# Buck_Sense.net
KiCad netlist of a schematic drawn in Altium Designer
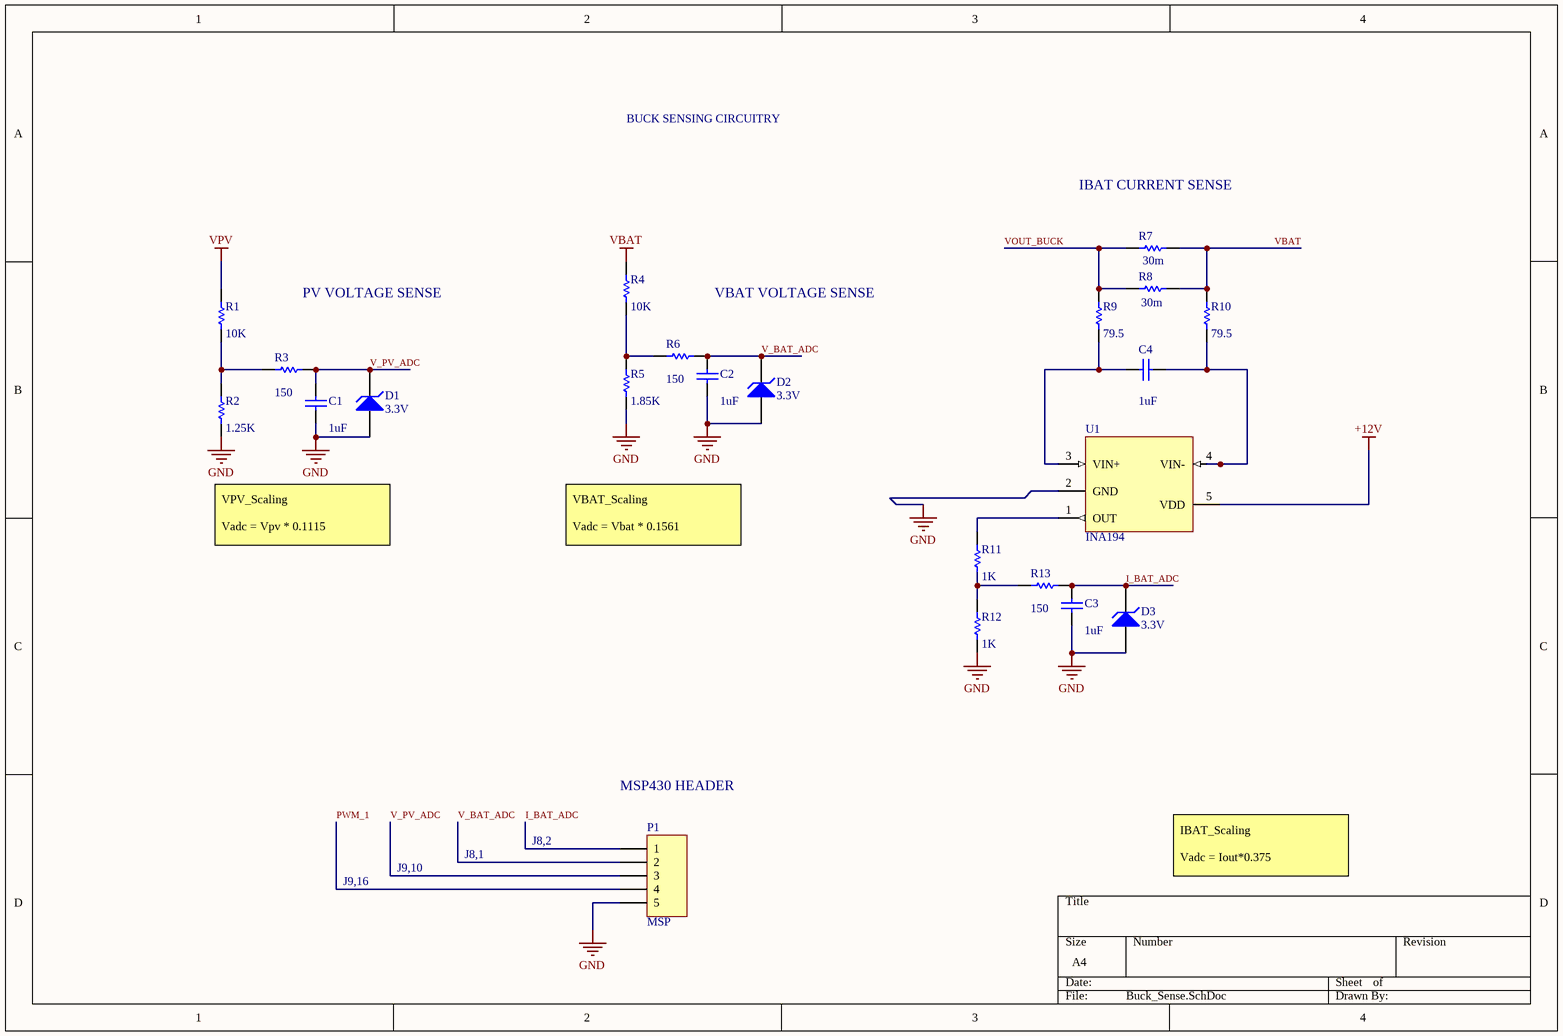
[diagram p0: Buck_Sense.SchDoc]

(export (version "E")
  (design (tool "Eeschema 10.0.6"))
  (components
    (comp (ref "C1")
      (value "1uF")
      (footprint "RAD-0.3")
      (description "Capacitor")
      (fields (field (name "PUBLISHER") "Altium Limited"))
      (libsource (lib "Miscellaneous Devices") (part "Cap"))
    )
    (comp (ref "C2")
      (value "1uF")
      (footprint "RAD-0.3")
      (description "Capacitor")
      (fields (field (name "PUBLISHER") "Altium Limited"))
      (libsource (lib "Miscellaneous Devices") (part "Cap"))
    )
    (comp (ref "C3")
      (value "1uF")
      (footprint "RAD-0.3")
      (description "Capacitor")
      (fields (field (name "PUBLISHER") "Altium Limited"))
      (libsource (lib "Miscellaneous Devices") (part "Cap"))
    )
    (comp (ref "C4")
      (value "1uF")
      (footprint "RAD-0.3")
      (description "Capacitor")
      (fields (field (name "PUBLISHER") "Altium Limited"))
      (libsource (lib "Miscellaneous Devices") (part "Cap"))
    )
    (comp (ref "D1")
      (value "3.3V")
      (footprint "DIODE-0.7")
      (description "Zener Diode")
      (fields (field (name "PUBLISHER") "Altium Limited"))
      (libsource (lib "Miscellaneous Devices") (part "D Zener"))
    )
    (comp (ref "D2")
      (value "3.3V")
      (footprint "DIODE-0.7")
      (description "Zener Diode")
      (fields (field (name "PUBLISHER") "Altium Limited"))
      (libsource (lib "Miscellaneous Devices") (part "D Zener"))
    )
    (comp (ref "D3")
      (value "3.3V")
      (footprint "DIODE-0.7")
      (description "Zener Diode")
      (fields (field (name "PUBLISHER") "Altium Limited"))
      (libsource (lib "Miscellaneous Devices") (part "D Zener"))
    )
    (comp (ref "P1")
      (value "MSP")
      (footprint "HDR1X5")
      (description "Header, 5-Pin")
      (fields (field (name "PUBLISHER") "Altium Limited"))
      (libsource (lib "Miscellaneous Connectors") (part "Header 5"))
    )
    (comp (ref "R1")
      (value "10K")
      (footprint "AXIAL-0.3")
      (description "Resistor")
      (fields (field (name "PUBLISHER") "Altium Limited"))
      (libsource (lib "Miscellaneous Devices") (part "Res1"))
    )
    (comp (ref "R2")
      (value "1.25K")
      (footprint "AXIAL-0.3")
      (description "Resistor")
      (fields (field (name "PUBLISHER") "Altium Limited"))
      (libsource (lib "Miscellaneous Devices") (part "Res1"))
    )
    (comp (ref "R3")
      (value "150")
      (footprint "AXIAL-0.3")
      (description "Resistor")
      (fields (field (name "PUBLISHER") "Altium Limited"))
      (libsource (lib "Miscellaneous Devices") (part "Res1"))
    )
    (comp (ref "R4")
      (value "10K")
      (footprint "AXIAL-0.3")
      (description "Resistor")
      (fields (field (name "PUBLISHER") "Altium Limited"))
      (libsource (lib "Miscellaneous Devices") (part "Res1"))
    )
    (comp (ref "R5")
      (value "1.85K")
      (footprint "AXIAL-0.3")
      (description "Resistor")
      (fields (field (name "PUBLISHER") "Altium Limited"))
      (libsource (lib "Miscellaneous Devices") (part "Res1"))
    )
    (comp (ref "R6")
      (value "150")
      (footprint "AXIAL-0.3")
      (description "Resistor")
      (fields (field (name "PUBLISHER") "Altium Limited"))
      (libsource (lib "Miscellaneous Devices") (part "Res1"))
    )
    (comp (ref "R7")
      (value "30m")
      (footprint "AXIAL-0.3")
      (description "Resistor")
      (fields (field (name "PUBLISHER") "Altium Limited"))
      (libsource (lib "Miscellaneous Devices") (part "Res1"))
    )
    (comp (ref "R8")
      (value "30m")
      (footprint "AXIAL-0.3")
      (description "Resistor")
      (fields (field (name "PUBLISHER") "Altium Limited"))
      (libsource (lib "Miscellaneous Devices") (part "Res1"))
    )
    (comp (ref "R9")
      (value "79.5")
      (footprint "AXIAL-0.3")
      (description "Resistor")
      (fields (field (name "PUBLISHER") "Altium Limited"))
      (libsource (lib "Miscellaneous Devices") (part "Res1"))
    )
    (comp (ref "R10")
      (value "79.5")
      (footprint "AXIAL-0.3")
      (description "Resistor")
      (fields (field (name "PUBLISHER") "Altium Limited"))
      (libsource (lib "Miscellaneous Devices") (part "Res1"))
    )
    (comp (ref "R11")
      (value "1K")
      (footprint "AXIAL-0.3")
      (description "Resistor")
      (fields (field (name "PUBLISHER") "Altium Limited"))
      (libsource (lib "Miscellaneous Devices") (part "Res1"))
    )
    (comp (ref "R12")
      (value "1K")
      (footprint "AXIAL-0.3")
      (description "Resistor")
      (fields (field (name "PUBLISHER") "Altium Limited"))
      (libsource (lib "Miscellaneous Devices") (part "Res1"))
    )
    (comp (ref "R13")
      (value "150")
      (footprint "AXIAL-0.3")
      (description "Resistor")
      (fields (field (name "PUBLISHER") "Altium Limited"))
      (libsource (lib "Miscellaneous Devices") (part "Res1"))
    )
    (comp (ref "U1")
      (value "INA194")
      (description "CURRENT SHUNT MONITOR")
      (libsource (lib "*") (part "INA194"))
    )
  )
  (nets
    (net (code "1") (name "+12V") (class "Default")
      (node (ref "U1") (pin "5") (pinfunction "VDD_5") (pintype "power_in"))
    )
    (net (code "2") (name "/I_BAT_ADC") (class "Default")
      (node (ref "C3") (pin "2") (pinfunction "2_2") (pintype "passive"))
      (node (ref "D3") (pin "2") (pinfunction "K_2") (pintype "passive"))
      (node (ref "P1") (pin "1") (pinfunction "1_1") (pintype "passive"))
      (node (ref "R13") (pin "2") (pinfunction "2_2") (pintype "passive"))
    )
    (net (code "3") (name "/PWM_1") (class "Default")
      (node (ref "P1") (pin "4") (pinfunction "4_4") (pintype "passive"))
    )
    (net (code "4") (name "/VOUT_BUCK") (class "Default")
      (node (ref "R7") (pin "2") (pinfunction "2_2") (pintype "passive"))
      (node (ref "R8") (pin "2") (pinfunction "2_2") (pintype "passive"))
      (node (ref "R9") (pin "1") (pinfunction "1_1") (pintype "passive"))
    )
    (net (code "5") (name "/V_BAT_ADC") (class "Default")
      (node (ref "C2") (pin "2") (pinfunction "2_2") (pintype "passive"))
      (node (ref "D2") (pin "2") (pinfunction "K_2") (pintype "passive"))
      (node (ref "P1") (pin "2") (pinfunction "2_2") (pintype "passive"))
      (node (ref "R6") (pin "1") (pinfunction "1_1") (pintype "passive"))
    )
    (net (code "6") (name "/V_PV_ADC") (class "Default")
      (node (ref "C1") (pin "2") (pinfunction "2_2") (pintype "passive"))
      (node (ref "D1") (pin "2") (pinfunction "K_2") (pintype "passive"))
      (node (ref "P1") (pin "3") (pinfunction "3_3") (pintype "passive"))
      (node (ref "R3") (pin "2") (pinfunction "2_2") (pintype "passive"))
    )
    (net (code "7") (name "GND") (class "Default")
      (node (ref "C1") (pin "1") (pinfunction "1_1") (pintype "passive"))
      (node (ref "C2") (pin "1") (pinfunction "1_1") (pintype "passive"))
      (node (ref "C3") (pin "1") (pinfunction "1_1") (pintype "passive"))
      (node (ref "D1") (pin "1") (pinfunction "A_1") (pintype "passive"))
      (node (ref "D2") (pin "1") (pinfunction "A_1") (pintype "passive"))
      (node (ref "D3") (pin "1") (pinfunction "A_1") (pintype "passive"))
      (node (ref "P1") (pin "5") (pinfunction "5_5") (pintype "passive"))
      (node (ref "R12") (pin "2") (pinfunction "2_2") (pintype "passive"))
      (node (ref "R2") (pin "1") (pinfunction "1_1") (pintype "passive"))
      (node (ref "R5") (pin "1") (pinfunction "1_1") (pintype "passive"))
      (node (ref "U1") (pin "2") (pinfunction "GND_2") (pintype "power_in"))
    )
    (net (code "8") (name "Net-(R1-Pad1)") (class "Default")
      (node (ref "R1") (pin "1") (pinfunction "1_1") (pintype "passive"))
      (node (ref "R2") (pin "2") (pinfunction "2_2") (pintype "passive"))
      (node (ref "R3") (pin "1") (pinfunction "1_1") (pintype "passive"))
    )
    (net (code "9") (name "Net-(R4-Pad1)") (class "Default")
      (node (ref "R4") (pin "1") (pinfunction "1_1") (pintype "passive"))
      (node (ref "R5") (pin "2") (pinfunction "2_2") (pintype "passive"))
      (node (ref "R6") (pin "2") (pinfunction "2_2") (pintype "passive"))
    )
    (net (code "10") (name "Net-(R11-Pad2)") (class "Default")
      (node (ref "R11") (pin "2") (pinfunction "2_2") (pintype "passive"))
      (node (ref "R12") (pin "1") (pinfunction "1_1") (pintype "passive"))
      (node (ref "R13") (pin "1") (pinfunction "1_1") (pintype "passive"))
    )
    (net (code "11") (name "Net-(U1-OUT)") (class "Default")
      (node (ref "R11") (pin "1") (pinfunction "1_1") (pintype "passive"))
      (node (ref "U1") (pin "1") (pinfunction "OUT_1") (pintype "output"))
    )
    (net (code "12") (name "Net-(U1-VIN+)") (class "Default")
      (node (ref "C4") (pin "2") (pinfunction "2_2") (pintype "passive"))
      (node (ref "R9") (pin "2") (pinfunction "2_2") (pintype "passive"))
      (node (ref "U1") (pin "3") (pinfunction "VIN+_3") (pintype "input"))
    )
    (net (code "13") (name "Net-(U1-VIN-)") (class "Default")
      (node (ref "C4") (pin "1") (pinfunction "1_1") (pintype "passive"))
      (node (ref "R10") (pin "2") (pinfunction "2_2") (pintype "passive"))
      (node (ref "U1") (pin "4") (pinfunction "VIN-_4") (pintype "input"))
    )
    (net (code "14") (name "VBAT") (class "Default")
      (node (ref "R10") (pin "1") (pinfunction "1_1") (pintype "passive"))
      (node (ref "R4") (pin "2") (pinfunction "2_2") (pintype "passive"))
      (node (ref "R7") (pin "1") (pinfunction "1_1") (pintype "passive"))
      (node (ref "R8") (pin "1") (pinfunction "1_1") (pintype "passive"))
    )
    (net (code "15") (name "VPV") (class "Default")
      (node (ref "R1") (pin "2") (pinfunction "2_2") (pintype "passive"))
    )
  )
)
